# SCH_PoC_Interrupt_Jao_2023-12-15.net
KiCad netlist of a schematic drawn in EasyEDA
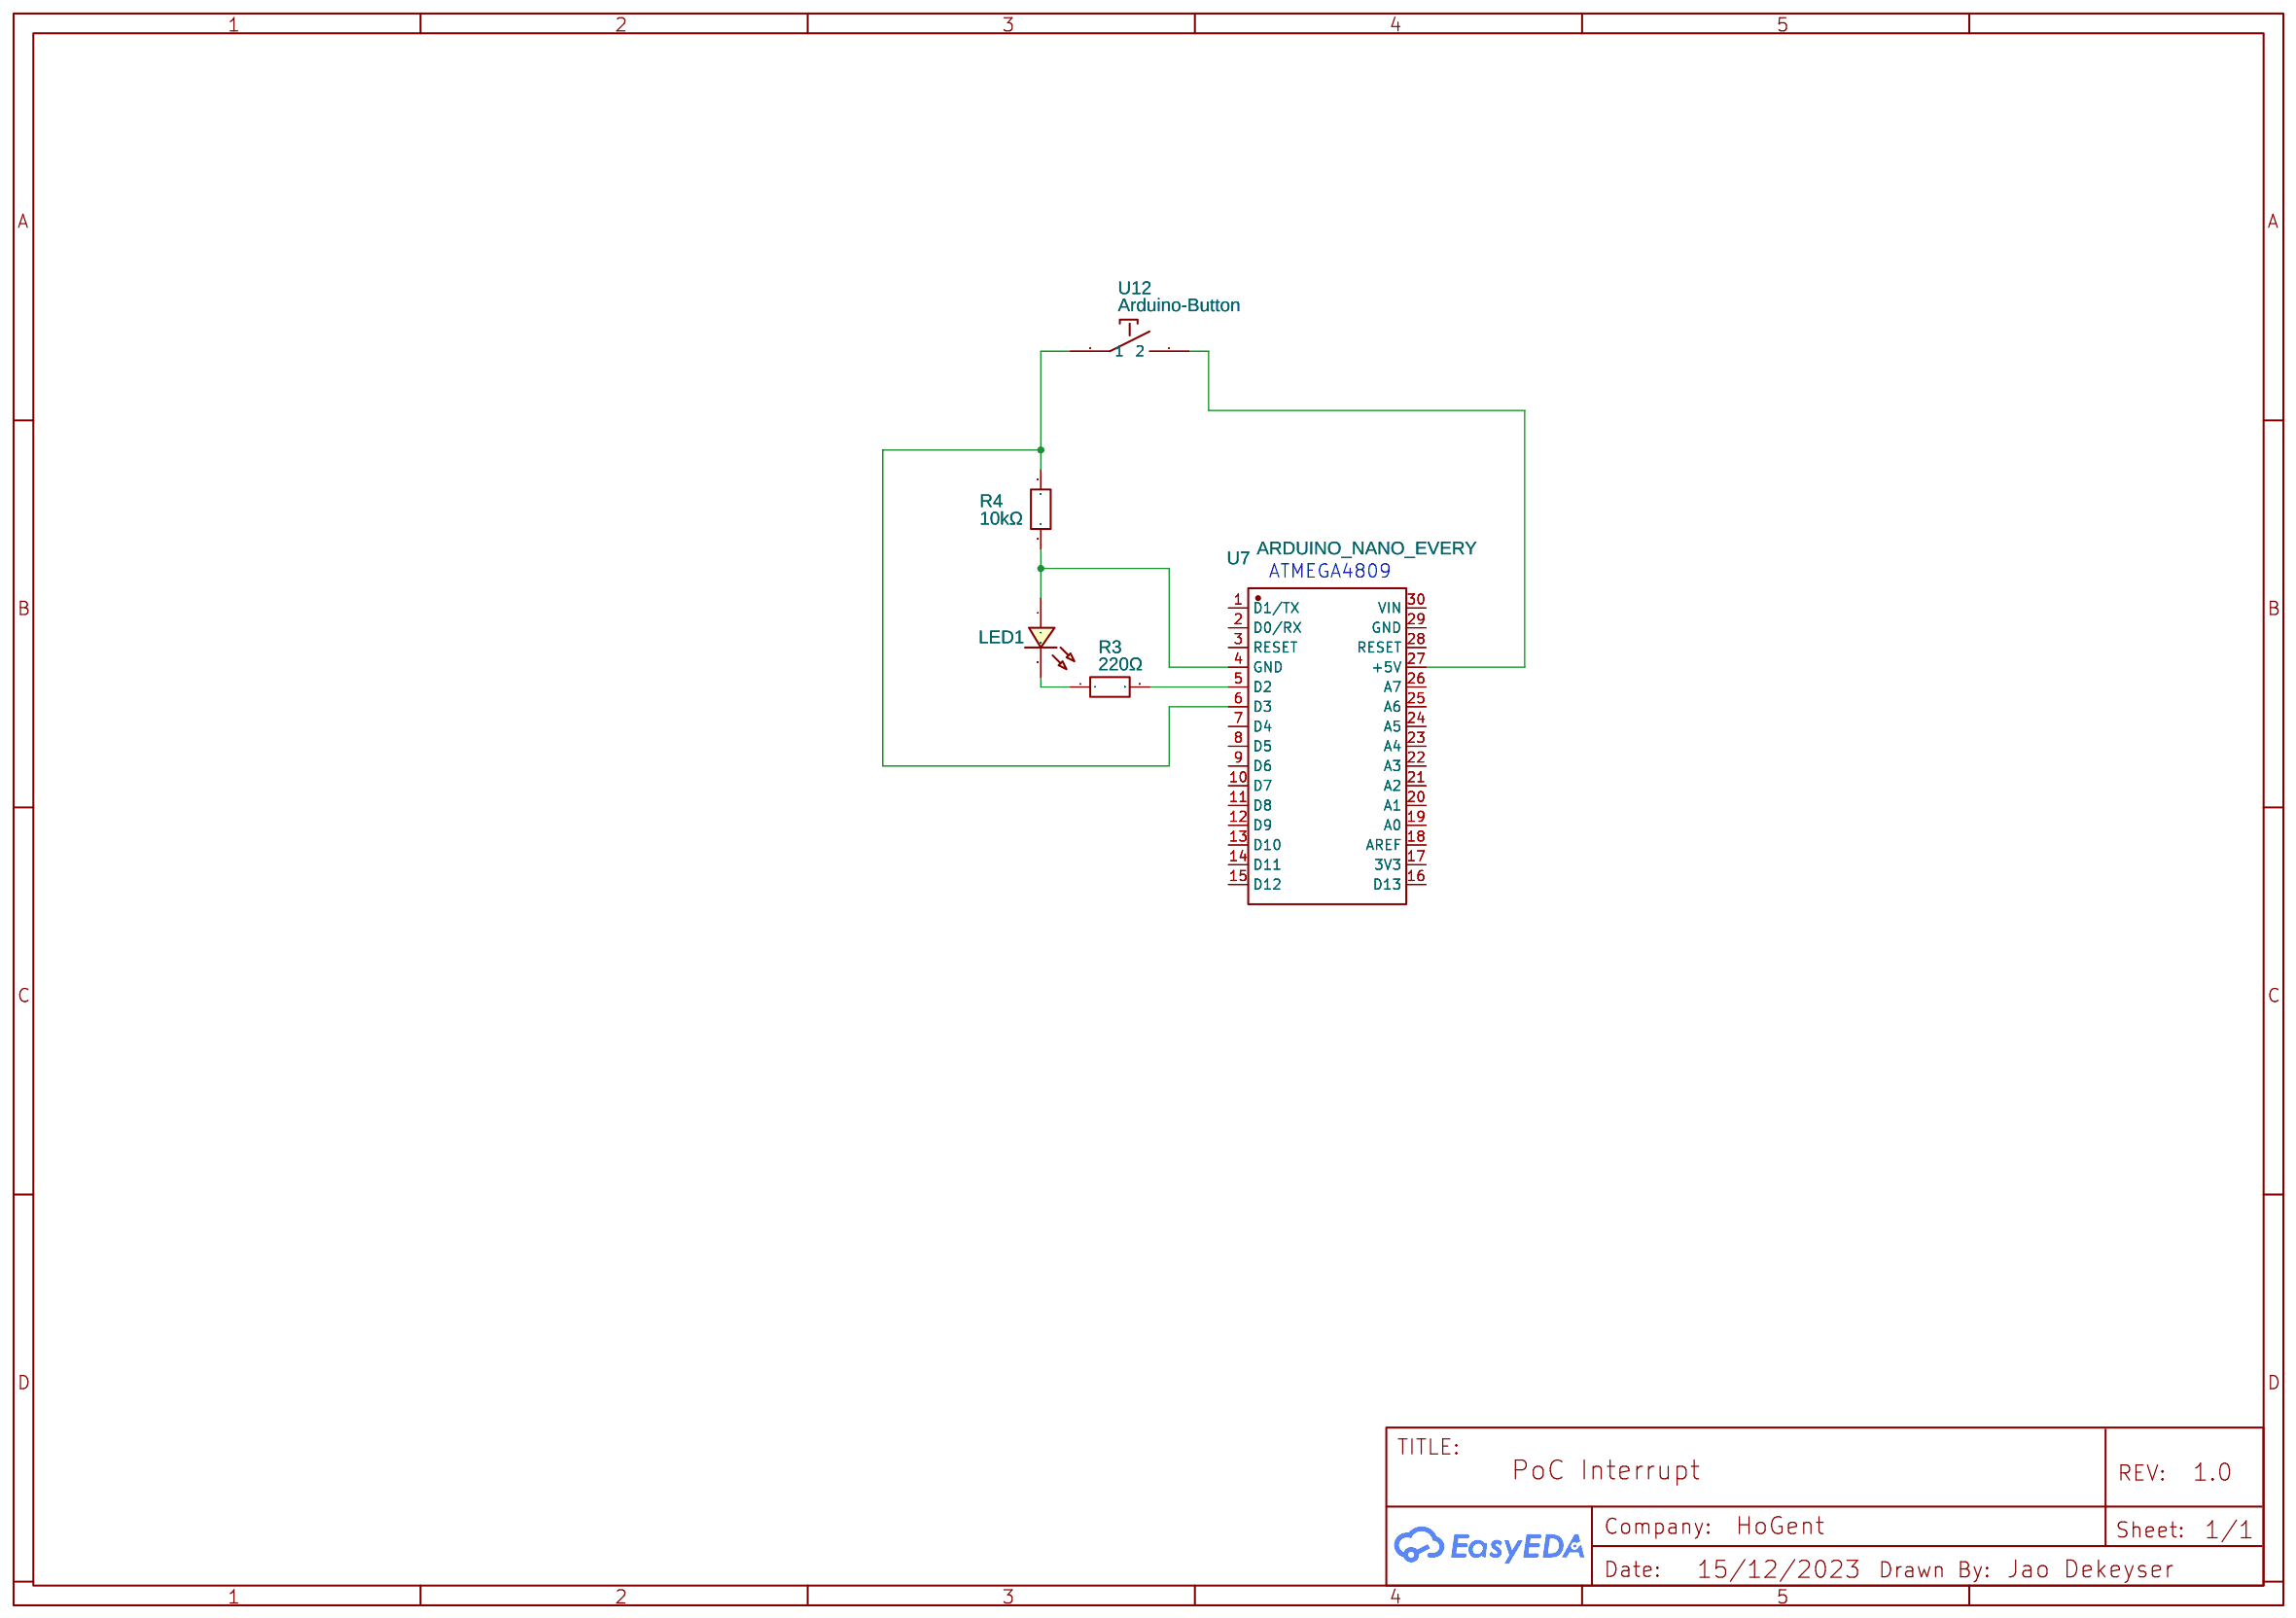
[diagram p0: schematic sheet]

(export (version "E")
  (design (tool "Eeschema 10.0.6"))
  (components
    (comp (ref "LED1")
      (value "LED-TH-5mm_R")
      (fields
        (field (name "Manufacturer Part") "333-2SURD/S530-A3")
        (field (name "Manufacturer") "EVERLIGHT(台湾亿光)")
      )
      (libsource (lib "") (part "LED-TH-5mm_R"))
    )
    (comp (ref "R3")
      (value "220Ω")
      (libsource (lib "") (part "AXIAL RESISTOR 220 OHM - TH_BD2.3-L6.0-P10.00-D0.4_1"))
    )
    (comp (ref "R4")
      (value "10kΩ")
      (libsource (lib "") (part "AXIAL RESISTOR 220 OHM - TH_BD2.3-L6.0-P10.00-D0.4"))
    )
    (comp (ref "U7")
      (value "ARDUINO_NANO_EVERY")
      (fields (field (name "Manufacturer Part") "ARDUINO_NANO"))
      (libsource (lib "") (part "ARDUINO_NANO"))
    )
    (comp (ref "U12")
      (value "Arduino-Button")
      (fields (field (name "Manufacturer Part") "SW100664"))
      (libsource (lib "") (part "Arduino-Button"))
    )
  )
  (nets
    (net (code "1") (name "Net-(LED1-Pad1)") (class "Default")
      (node (ref "LED1") (pin "1") (pinfunction "1_1") (pintype "unspecified"))
      (node (ref "R4") (pin "1") (pinfunction "1_1") (pintype "unspecified"))
      (node (ref "U7") (pin "4") (pinfunction "GND_4") (pintype "unspecified"))
    )
    (net (code "2") (name "Net-(LED1-Pad2)") (class "Default")
      (node (ref "LED1") (pin "2") (pinfunction "2_2") (pintype "unspecified"))
      (node (ref "R3") (pin "1") (pinfunction "1_1") (pintype "unspecified"))
    )
    (net (code "3") (name "Net-(U7-+5V)") (class "Default")
      (node (ref "U12") (pin "2") (pinfunction "2_2") (pintype "unspecified"))
      (node (ref "U7") (pin "27") (pinfunction "+5V_27") (pintype "unspecified"))
    )
    (net (code "4") (name "Net-(U7-D2)") (class "Default")
      (node (ref "R3") (pin "2") (pinfunction "2_2") (pintype "unspecified"))
      (node (ref "U7") (pin "5") (pinfunction "D2_5") (pintype "unspecified"))
    )
    (net (code "5") (name "Net-(U7-D3)") (class "Default")
      (node (ref "R4") (pin "2") (pinfunction "2_2") (pintype "unspecified"))
      (node (ref "U12") (pin "1") (pinfunction "1_1") (pintype "unspecified"))
      (node (ref "U7") (pin "6") (pinfunction "D3_6") (pintype "unspecified"))
    )
    (net (code "6") (name "unconnected-(U7-3V3-Pad17)") (class "Default")
      (node (ref "U7") (pin "17") (pinfunction "3V3_17") (pintype "unspecified"))
    )
    (net (code "7") (name "unconnected-(U7-A0-Pad19)") (class "Default")
      (node (ref "U7") (pin "19") (pinfunction "A0_19") (pintype "unspecified"))
    )
    (net (code "8") (name "unconnected-(U7-A1-Pad20)") (class "Default")
      (node (ref "U7") (pin "20") (pinfunction "A1_20") (pintype "unspecified"))
    )
    (net (code "9") (name "unconnected-(U7-A2-Pad21)") (class "Default")
      (node (ref "U7") (pin "21") (pinfunction "A2_21") (pintype "unspecified"))
    )
    (net (code "10") (name "unconnected-(U7-A3-Pad22)") (class "Default")
      (node (ref "U7") (pin "22") (pinfunction "A3_22") (pintype "unspecified"))
    )
    (net (code "11") (name "unconnected-(U7-A4-Pad23)") (class "Default")
      (node (ref "U7") (pin "23") (pinfunction "A4_23") (pintype "unspecified"))
    )
    (net (code "12") (name "unconnected-(U7-A5-Pad24)") (class "Default")
      (node (ref "U7") (pin "24") (pinfunction "A5_24") (pintype "unspecified"))
    )
    (net (code "13") (name "unconnected-(U7-A6-Pad25)") (class "Default")
      (node (ref "U7") (pin "25") (pinfunction "A6_25") (pintype "unspecified"))
    )
    (net (code "14") (name "unconnected-(U7-A7-Pad26)") (class "Default")
      (node (ref "U7") (pin "26") (pinfunction "A7_26") (pintype "unspecified"))
    )
    (net (code "15") (name "unconnected-(U7-AREF-Pad18)") (class "Default")
      (node (ref "U7") (pin "18") (pinfunction "AREF_18") (pintype "unspecified"))
    )
    (net (code "16") (name "unconnected-(U7-D0{slash}RX-Pad2)") (class "Default")
      (node (ref "U7") (pin "2") (pinfunction "D0/RX_2") (pintype "unspecified"))
    )
    (net (code "17") (name "unconnected-(U7-D1{slash}TX-Pad1)") (class "Default")
      (node (ref "U7") (pin "1") (pinfunction "D1/TX_1") (pintype "unspecified"))
    )
    (net (code "18") (name "unconnected-(U7-D4-Pad7)") (class "Default")
      (node (ref "U7") (pin "7") (pinfunction "D4_7") (pintype "unspecified"))
    )
    (net (code "19") (name "unconnected-(U7-D5-Pad8)") (class "Default")
      (node (ref "U7") (pin "8") (pinfunction "D5_8") (pintype "unspecified"))
    )
    (net (code "20") (name "unconnected-(U7-D6-Pad9)") (class "Default")
      (node (ref "U7") (pin "9") (pinfunction "D6_9") (pintype "unspecified"))
    )
    (net (code "21") (name "unconnected-(U7-D7-Pad10)") (class "Default")
      (node (ref "U7") (pin "10") (pinfunction "D7_10") (pintype "unspecified"))
    )
    (net (code "22") (name "unconnected-(U7-D8-Pad11)") (class "Default")
      (node (ref "U7") (pin "11") (pinfunction "D8_11") (pintype "unspecified"))
    )
    (net (code "23") (name "unconnected-(U7-D9-Pad12)") (class "Default")
      (node (ref "U7") (pin "12") (pinfunction "D9_12") (pintype "unspecified"))
    )
    (net (code "24") (name "unconnected-(U7-D10-Pad13)") (class "Default")
      (node (ref "U7") (pin "13") (pinfunction "D10_13") (pintype "unspecified"))
    )
    (net (code "25") (name "unconnected-(U7-D11-Pad14)") (class "Default")
      (node (ref "U7") (pin "14") (pinfunction "D11_14") (pintype "unspecified"))
    )
    (net (code "26") (name "unconnected-(U7-D12-Pad15)") (class "Default")
      (node (ref "U7") (pin "15") (pinfunction "D12_15") (pintype "unspecified"))
    )
    (net (code "27") (name "unconnected-(U7-D13-Pad16)") (class "Default")
      (node (ref "U7") (pin "16") (pinfunction "D13_16") (pintype "unspecified"))
    )
    (net (code "28") (name "unconnected-(U7-GND-Pad29)") (class "Default")
      (node (ref "U7") (pin "29") (pinfunction "GND_29") (pintype "unspecified"))
    )
    (net (code "29") (name "unconnected-(U7-RESET-Pad3)") (class "Default")
      (node (ref "U7") (pin "3") (pinfunction "RESET_3") (pintype "unspecified"))
    )
    (net (code "30") (name "unconnected-(U7-RESET-Pad28)") (class "Default")
      (node (ref "U7") (pin "28") (pinfunction "RESET_28") (pintype "unspecified"))
    )
    (net (code "31") (name "unconnected-(U7-VIN-Pad30)") (class "Default")
      (node (ref "U7") (pin "30") (pinfunction "VIN_30") (pintype "unspecified"))
    )
  )
)
